# -.net
KiCad netlist of a schematic drawn in EasyEDA Pro
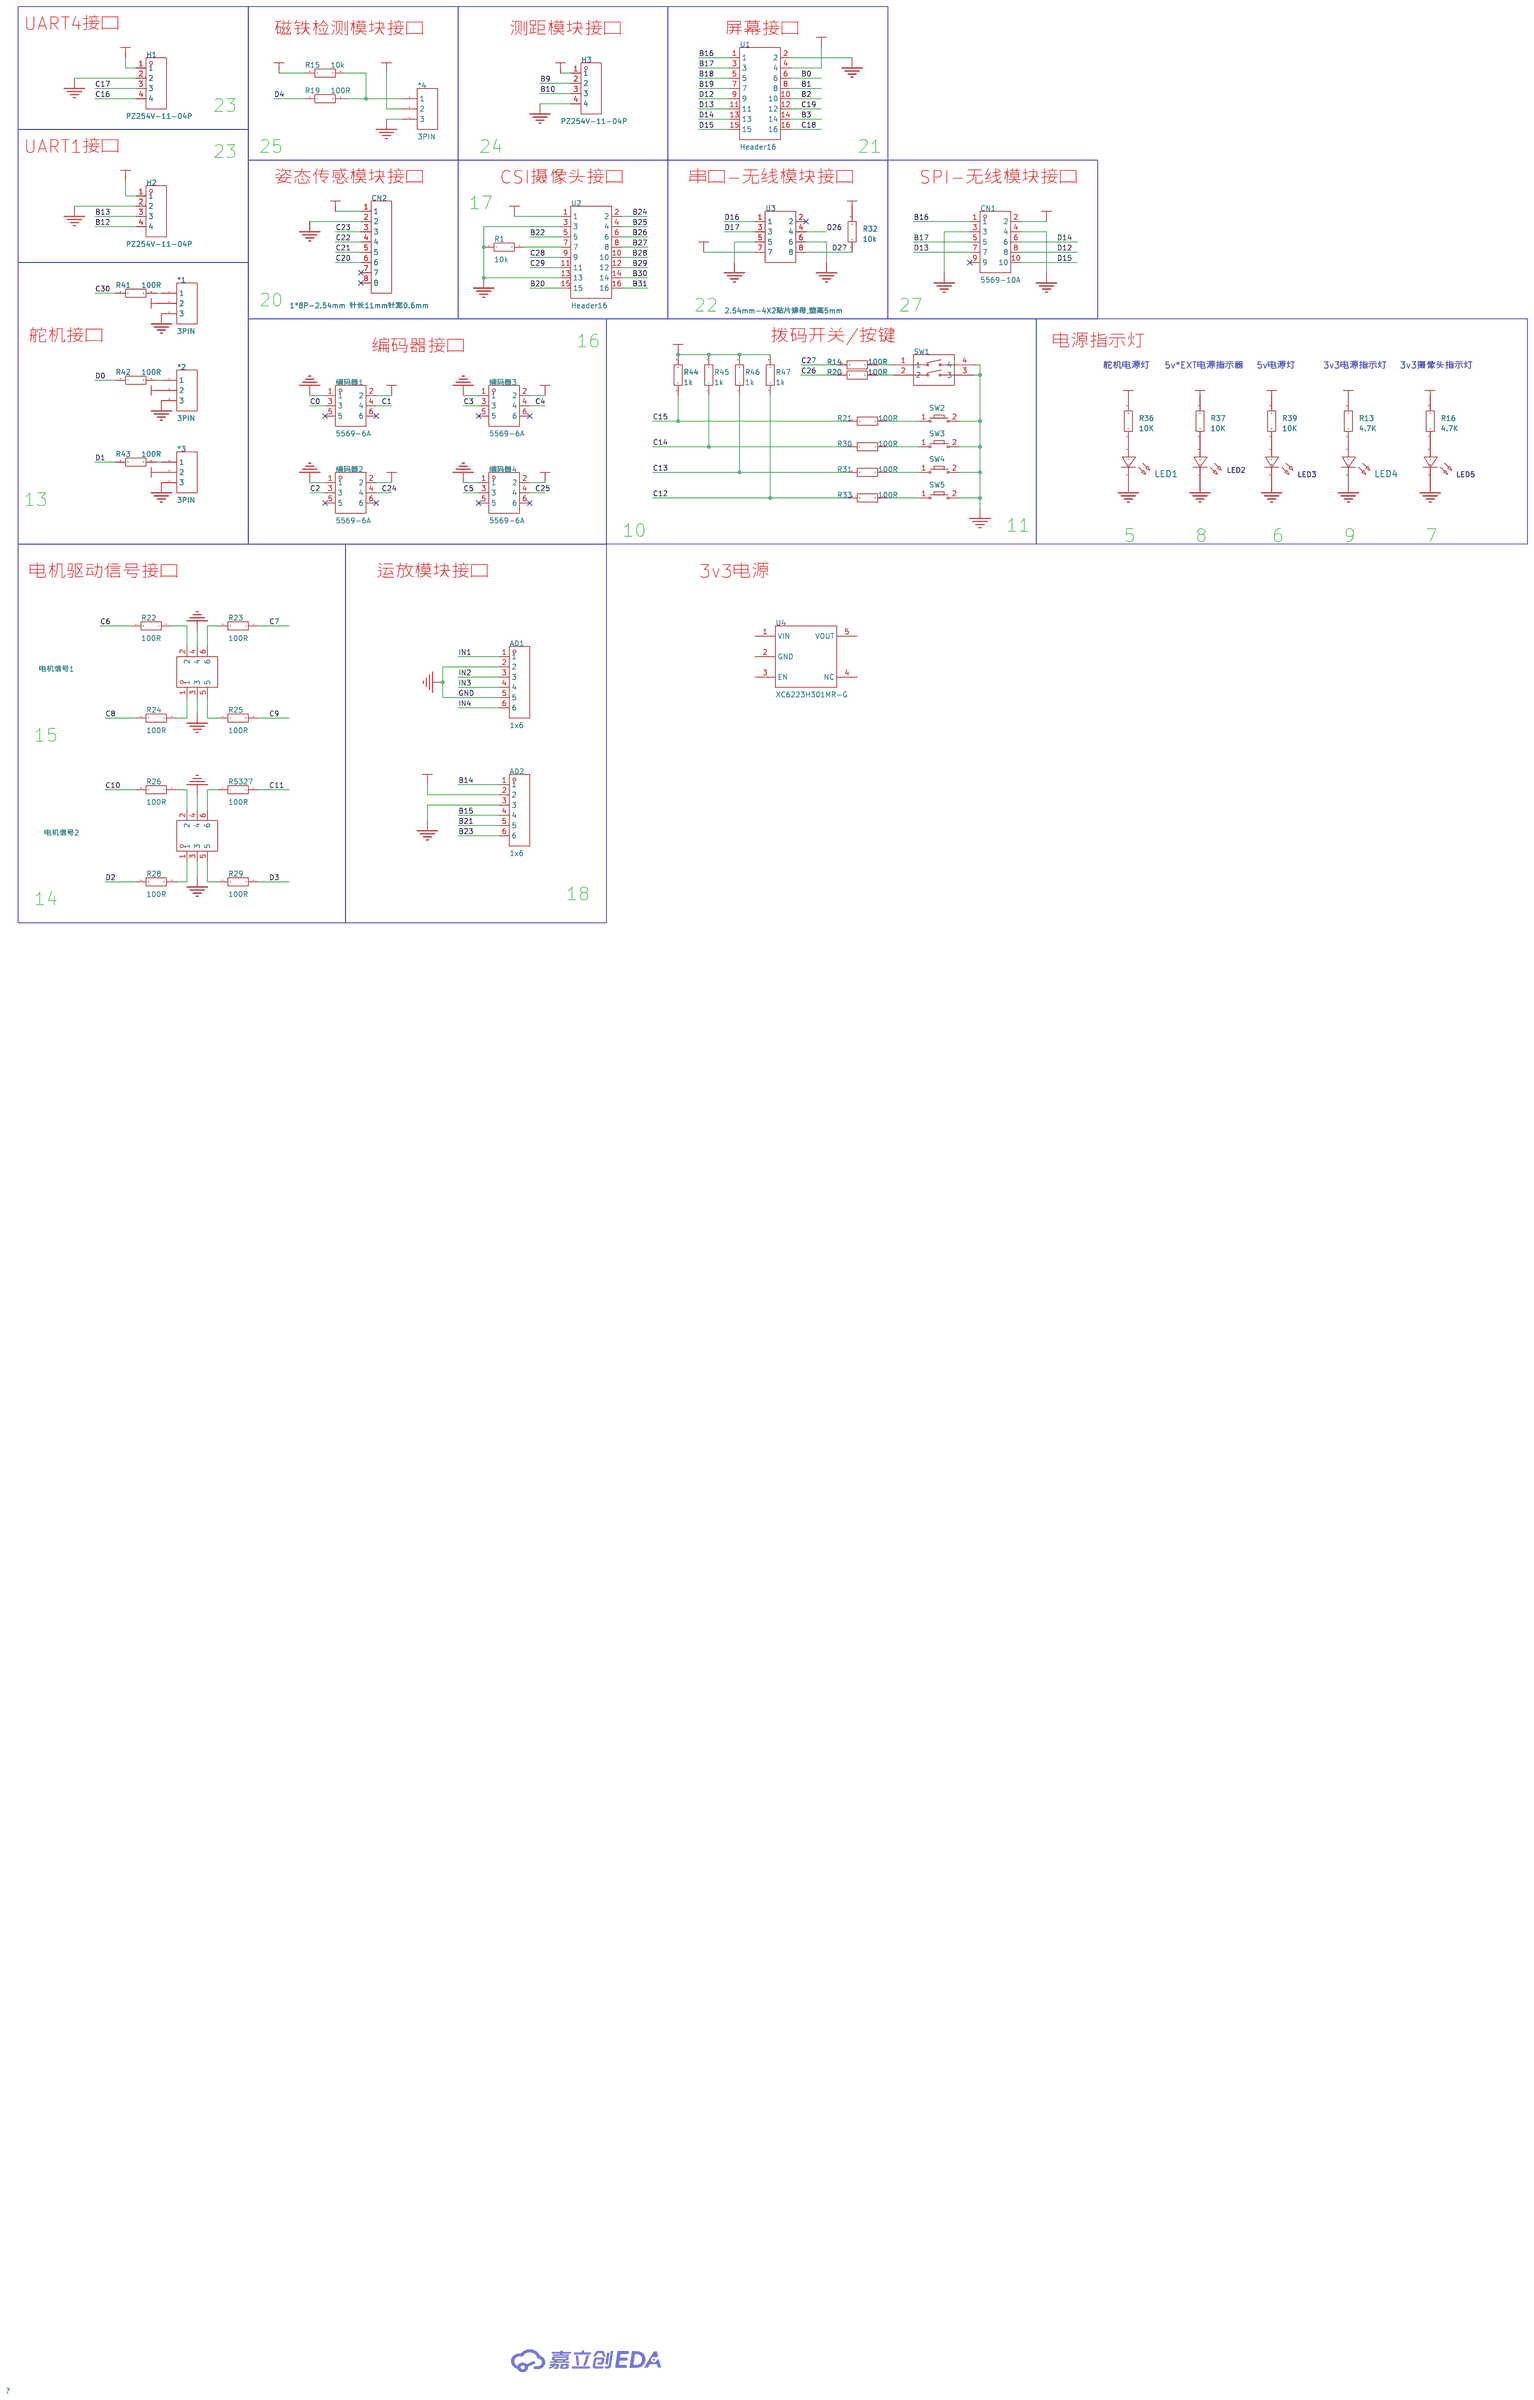
[diagram p0: schematic sheet]

(export (version "E")
  (design (tool "Eeschema 10.0.6"))
  (components
    (comp (ref "*1")
      (value "3PIN")
      (footprint "easyedapro:3PIN")
      (libsource (lib "easyedapro") (part "1*3PIN"))
    )
    (comp (ref "*2")
      (value "3PIN")
      (footprint "easyedapro:3PIN")
      (libsource (lib "easyedapro") (part "1*3PIN"))
    )
    (comp (ref "*3")
      (value "3PIN")
      (footprint "easyedapro:3PIN")
      (libsource (lib "easyedapro") (part "1*3PIN"))
    )
    (comp (ref "*4")
      (value "3PIN")
      (footprint "easyedapro:3PIN")
      (libsource (lib "easyedapro") (part "1*3PIN"))
    )
    (comp (ref "AD1")
      (value "1x6")
      (footprint "easyedapro:HDR-TH_6P-P2.54-V-F")
      (fields (field (name "Manufacturer Part") "Female header 1*6p") (field (name "Manufacturer") "BOOMELE"))
      (libsource (lib "easyedapro") (part "1x6"))
    )
    (comp (ref "AD2")
      (value "1x6")
      (footprint "easyedapro:HDR-TH_6P-P2.54-V-F")
      (fields (field (name "Manufacturer Part") "Female header 1*6p") (field (name "Manufacturer") "BOOMELE"))
      (libsource (lib "easyedapro") (part "1x6"))
    )
    (comp (ref "CN1")
      (value "5569-10A")
      (footprint "easyedapro:CONN-TH_10P-P4.20_5569-10A")
      (libsource (lib "easyedapro") (part "5569-10A"))
    )
    (comp (ref "CN2")
      (value "1*8P-2.54mm 针长11mm针宽0.6mm")
      (footprint "easyedapro:HDR-TH_8P-P2.54-V-F-S2.54")
      (libsource (lib "easyedapro") (part "1*8P-2.54MM 针长11MM针宽0.6MM"))
    )
    (comp (ref "H1")
      (value "PZ254V-11-04P")
      (footprint "easyedapro:HDR-TH_4P-P2.54-V-M")
      (fields (field (name "Manufacturer") "XFCN(兴飞)"))
      (libsource (lib "easyedapro") (part "PZ254V-11-04P_C2691448"))
    )
    (comp (ref "H2")
      (value "PZ254V-11-04P")
      (footprint "easyedapro:HDR-TH_4P-P2.54-V-M")
      (fields (field (name "Manufacturer") "XFCN(兴飞)"))
      (libsource (lib "easyedapro") (part "PZ254V-11-04P_C2691448"))
    )
    (comp (ref "H3")
      (value "PZ254V-11-04P")
      (footprint "easyedapro:HDR-TH_4P-P2.54-V-M")
      (fields (field (name "Manufacturer") "XFCN(兴飞)"))
      (libsource (lib "easyedapro") (part "PZ254V-11-04P_C2691448"))
    )
    (comp (ref "LED1")
      (value "~")
      (footprint "easyedapro:LED_0603")
      (libsource (lib "easyedapro") (part "LED_R"))
    )
    (comp (ref "LED2")
      (value "~")
      (footprint "easyedapro:LED_0603")
      (libsource (lib "easyedapro") (part "LED_G"))
    )
    (comp (ref "LED3")
      (value "~")
      (footprint "easyedapro:LED_0603")
      (libsource (lib "easyedapro") (part "LED_B"))
    )
    (comp (ref "LED4")
      (value "~")
      (footprint "easyedapro:LED_0603")
      (libsource (lib "easyedapro") (part "LED_R"))
    )
    (comp (ref "LED5")
      (value "~")
      (footprint "easyedapro:LED_0603")
      (libsource (lib "easyedapro") (part "LED_G"))
    )
    (comp (ref "R1")
      (value "10k")
      (footprint "easyedapro:R0603")
      (description "电阻类型:厚膜电阻;阻值:10kΩ;精度:±1%;功率:100mW;工作电压:75V;温度系数:±100ppm/°C;")
      (fields
        (field (name "Manufacturer Part") "0603WAF1002T5E")
        (field (name "Manufacturer") "UNI-ROYAL(厚声)")
      )
      (libsource (lib "easyedapro") (part "0603WAF1002T5E"))
    )
    (comp (ref "R13")
      (value "4.7K")
      (footprint "easyedapro:R0603")
      (libsource (lib "easyedapro") (part "电阻"))
    )
    (comp (ref "R14")
      (value "100Ω ±1% 62.5mW")
      (footprint "easyedapro:R0402")
      (fields
        (field (name "Manufacturer Part") "0402WGF1000TCE")
        (field (name "Manufacturer") "UNI-ROYAL(厚声)")
      )
      (libsource (lib "easyedapro") (part "0402WGF1000TCE"))
    )
    (comp (ref "R15")
      (value "10k")
      (footprint "easyedapro:R0603")
      (description "电阻类型:厚膜电阻;阻值:10kΩ;精度:±1%;功率:100mW;工作电压:75V;温度系数:±100ppm/°C;")
      (fields
        (field (name "Manufacturer Part") "0603WAF1002T5E")
        (field (name "Manufacturer") "UNI-ROYAL(厚声)")
      )
      (libsource (lib "easyedapro") (part "0603WAF1002T5E"))
    )
    (comp (ref "R16")
      (value "4.7K")
      (footprint "easyedapro:R0603")
      (libsource (lib "easyedapro") (part "电阻"))
    )
    (comp (ref "R19")
      (value "100Ω ±1% 62.5mW")
      (footprint "easyedapro:R0402")
      (fields
        (field (name "Manufacturer Part") "0402WGF1000TCE")
        (field (name "Manufacturer") "UNI-ROYAL(厚声)")
      )
      (libsource (lib "easyedapro") (part "0402WGF1000TCE"))
    )
    (comp (ref "R20")
      (value "100Ω ±1% 62.5mW")
      (footprint "easyedapro:R0402")
      (fields
        (field (name "Manufacturer Part") "0402WGF1000TCE")
        (field (name "Manufacturer") "UNI-ROYAL(厚声)")
      )
      (libsource (lib "easyedapro") (part "0402WGF1000TCE"))
    )
    (comp (ref "R21")
      (value "100Ω ±1% 62.5mW")
      (footprint "easyedapro:R0402")
      (fields
        (field (name "Manufacturer Part") "0402WGF1000TCE")
        (field (name "Manufacturer") "UNI-ROYAL(厚声)")
      )
      (libsource (lib "easyedapro") (part "0402WGF1000TCE"))
    )
    (comp (ref "R22")
      (value "100Ω ±1% 62.5mW")
      (footprint "easyedapro:R0402")
      (fields
        (field (name "Manufacturer Part") "0402WGF1000TCE")
        (field (name "Manufacturer") "UNI-ROYAL(厚声)")
      )
      (libsource (lib "easyedapro") (part "0402WGF1000TCE"))
    )
    (comp (ref "R23")
      (value "100Ω ±1% 62.5mW")
      (footprint "easyedapro:R0402")
      (fields
        (field (name "Manufacturer Part") "0402WGF1000TCE")
        (field (name "Manufacturer") "UNI-ROYAL(厚声)")
      )
      (libsource (lib "easyedapro") (part "0402WGF1000TCE"))
    )
    (comp (ref "R24")
      (value "100Ω ±1% 62.5mW")
      (footprint "easyedapro:R0402")
      (fields
        (field (name "Manufacturer Part") "0402WGF1000TCE")
        (field (name "Manufacturer") "UNI-ROYAL(厚声)")
      )
      (libsource (lib "easyedapro") (part "0402WGF1000TCE"))
    )
    (comp (ref "R25")
      (value "100Ω ±1% 62.5mW")
      (footprint "easyedapro:R0402")
      (fields
        (field (name "Manufacturer Part") "0402WGF1000TCE")
        (field (name "Manufacturer") "UNI-ROYAL(厚声)")
      )
      (libsource (lib "easyedapro") (part "0402WGF1000TCE"))
    )
    (comp (ref "R26")
      (value "100Ω ±1% 62.5mW")
      (footprint "easyedapro:R0402")
      (fields
        (field (name "Manufacturer Part") "0402WGF1000TCE")
        (field (name "Manufacturer") "UNI-ROYAL(厚声)")
      )
      (libsource (lib "easyedapro") (part "0402WGF1000TCE"))
    )
    (comp (ref "R28")
      (value "100Ω ±1% 62.5mW")
      (footprint "easyedapro:R0402")
      (fields
        (field (name "Manufacturer Part") "0402WGF1000TCE")
        (field (name "Manufacturer") "UNI-ROYAL(厚声)")
      )
      (libsource (lib "easyedapro") (part "0402WGF1000TCE"))
    )
    (comp (ref "R29")
      (value "100Ω ±1% 62.5mW")
      (footprint "easyedapro:R0402")
      (fields
        (field (name "Manufacturer Part") "0402WGF1000TCE")
        (field (name "Manufacturer") "UNI-ROYAL(厚声)")
      )
      (libsource (lib "easyedapro") (part "0402WGF1000TCE"))
    )
    (comp (ref "R30")
      (value "100Ω ±1% 62.5mW")
      (footprint "easyedapro:R0402")
      (fields
        (field (name "Manufacturer Part") "0402WGF1000TCE")
        (field (name "Manufacturer") "UNI-ROYAL(厚声)")
      )
      (libsource (lib "easyedapro") (part "0402WGF1000TCE"))
    )
    (comp (ref "R31")
      (value "100Ω ±1% 62.5mW")
      (footprint "easyedapro:R0402")
      (fields
        (field (name "Manufacturer Part") "0402WGF1000TCE")
        (field (name "Manufacturer") "UNI-ROYAL(厚声)")
      )
      (libsource (lib "easyedapro") (part "0402WGF1000TCE"))
    )
    (comp (ref "R32")
      (value "10k")
      (footprint "easyedapro:R0603")
      (description "电阻类型:厚膜电阻;阻值:10kΩ;精度:±1%;功率:100mW;工作电压:75V;温度系数:±100ppm/°C;")
      (fields
        (field (name "Manufacturer Part") "0603WAF1002T5E")
        (field (name "Manufacturer") "UNI-ROYAL(厚声)")
      )
      (libsource (lib "easyedapro") (part "0603WAF1002T5E"))
    )
    (comp (ref "R33")
      (value "100Ω ±1% 62.5mW")
      (footprint "easyedapro:R0402")
      (fields
        (field (name "Manufacturer Part") "0402WGF1000TCE")
        (field (name "Manufacturer") "UNI-ROYAL(厚声)")
      )
      (libsource (lib "easyedapro") (part "0402WGF1000TCE"))
    )
    (comp (ref "R36") (value "10K") (footprint "easyedapro:R0603") (libsource (lib "easyedapro") (part "电阻")))
    (comp (ref "R37") (value "10K") (footprint "easyedapro:R0603") (libsource (lib "easyedapro") (part "电阻")))
    (comp (ref "R39") (value "10K") (footprint "easyedapro:R0603") (libsource (lib "easyedapro") (part "电阻")))
    (comp (ref "R41")
      (value "100Ω ±1% 62.5mW")
      (footprint "easyedapro:R0402")
      (fields
        (field (name "Manufacturer Part") "0402WGF1000TCE")
        (field (name "Manufacturer") "UNI-ROYAL(厚声)")
      )
      (libsource (lib "easyedapro") (part "0402WGF1000TCE"))
    )
    (comp (ref "R42")
      (value "100Ω ±1% 62.5mW")
      (footprint "easyedapro:R0402")
      (fields
        (field (name "Manufacturer Part") "0402WGF1000TCE")
        (field (name "Manufacturer") "UNI-ROYAL(厚声)")
      )
      (libsource (lib "easyedapro") (part "0402WGF1000TCE"))
    )
    (comp (ref "R43")
      (value "100Ω ±1% 62.5mW")
      (footprint "easyedapro:R0402")
      (fields
        (field (name "Manufacturer Part") "0402WGF1000TCE")
        (field (name "Manufacturer") "UNI-ROYAL(厚声)")
      )
      (libsource (lib "easyedapro") (part "0402WGF1000TCE"))
    )
    (comp (ref "R44")
      (value "1k")
      (footprint "easyedapro:R0603")
      (description "电阻类型:厚膜电阻;阻值:10kΩ;精度:±1%;功率:100mW;工作电压:75V;温度系数:±100ppm/°C;")
      (fields
        (field (name "Manufacturer Part") "0603WAF1002T5E")
        (field (name "Manufacturer") "UNI-ROYAL(厚声)")
      )
      (libsource (lib "easyedapro") (part "0603WAF1002T5E"))
    )
    (comp (ref "R45")
      (value "1k")
      (footprint "easyedapro:R0603")
      (description "电阻类型:厚膜电阻;阻值:10kΩ;精度:±1%;功率:100mW;工作电压:75V;温度系数:±100ppm/°C;")
      (fields
        (field (name "Manufacturer Part") "0603WAF1002T5E")
        (field (name "Manufacturer") "UNI-ROYAL(厚声)")
      )
      (libsource (lib "easyedapro") (part "0603WAF1002T5E"))
    )
    (comp (ref "R46")
      (value "1k")
      (footprint "easyedapro:R0603")
      (description "电阻类型:厚膜电阻;阻值:10kΩ;精度:±1%;功率:100mW;工作电压:75V;温度系数:±100ppm/°C;")
      (fields
        (field (name "Manufacturer Part") "0603WAF1002T5E")
        (field (name "Manufacturer") "UNI-ROYAL(厚声)")
      )
      (libsource (lib "easyedapro") (part "0603WAF1002T5E"))
    )
    (comp (ref "R47")
      (value "1k")
      (footprint "easyedapro:R0603")
      (description "电阻类型:厚膜电阻;阻值:10kΩ;精度:±1%;功率:100mW;工作电压:75V;温度系数:±100ppm/°C;")
      (fields
        (field (name "Manufacturer Part") "0603WAF1002T5E")
        (field (name "Manufacturer") "UNI-ROYAL(厚声)")
      )
      (libsource (lib "easyedapro") (part "0603WAF1002T5E"))
    )
    (comp (ref "R5327")
      (value "100Ω ±1% 62.5mW")
      (footprint "easyedapro:R0402")
      (fields
        (field (name "Manufacturer Part") "0402WGF1000TCE")
        (field (name "Manufacturer") "UNI-ROYAL(厚声)")
      )
      (libsource (lib "easyedapro") (part "0402WGF1000TCE"))
    )
    (comp (ref "SW1")
      (value "CES-0202MC")
      (footprint "easyedapro:SW-TH_NIDEC_CES-0202MC")
      (description "特性：双镀金触点,接触稳定性极佳。符合RoHS标准。触感清脆。应用：热水设备。空调设备")
      (fields (field (name "Manufacturer") "NIDEC(尼得科)"))
      (libsource (lib "easyedapro") (part "CES-0202MC"))
    )
    (comp (ref "SW2")
      (value "~")
      (footprint "easyedapro:Key_SMD_3x4x2")
      (libsource (lib "easyedapro") (part "轻触按键x2"))
    )
    (comp (ref "SW3")
      (value "~")
      (footprint "easyedapro:Key_SMD_3x4x2")
      (libsource (lib "easyedapro") (part "轻触按键x2"))
    )
    (comp (ref "SW4")
      (value "~")
      (footprint "easyedapro:Key_SMD_3x4x2")
      (libsource (lib "easyedapro") (part "轻触按键x2"))
    )
    (comp (ref "SW5")
      (value "~")
      (footprint "easyedapro:Key_SMD_3x4x2")
      (libsource (lib "easyedapro") (part "轻触按键x2"))
    )
    (comp (ref "U1")
      (value "Header16")
      (footprint "easyedapro:CONN-TH_16P-P2.50_C9900044747")
      (libsource (lib "easyedapro") (part "HEADER16_C9900044747"))
    )
    (comp (ref "U2")
      (value "Header16")
      (footprint "easyedapro:CONN-TH_16P-P2.50_C9900044747")
      (libsource (lib "easyedapro") (part "HEADER16_C9900044747"))
    )
    (comp (ref "U3")
      (value "2.54mm-4X2贴片排母,塑高5mm")
      (footprint "easyedapro:HDR-SMD_8P-P2.54-V-F-R2-C4-S7.1")
      (libsource (lib "easyedapro") (part "2.54MM-4X2贴片排母,塑高5MM"))
    )
    (comp (ref "U4") (value "XC6223H301MR-G") (libsource (lib "easyedapro") (part "RT9013")))
    (comp (ref "电机信号1")
      (value "5569-6A")
      (footprint "easyedapro:CONN-TH_6P-P4.20_5569-6A-1")
      (libsource (lib "easyedapro") (part "5569-6A"))
    )
    (comp (ref "电机信号2")
      (value "5569-6A")
      (footprint "easyedapro:CONN-TH_6P-P4.20_5569-6A-1")
      (libsource (lib "easyedapro") (part "5569-6A"))
    )
    (comp (ref "编码器1")
      (value "5569-6A")
      (footprint "easyedapro:CONN-TH_6P-P4.20_5569-6A-1")
      (libsource (lib "easyedapro") (part "5569-6A"))
    )
    (comp (ref "编码器2")
      (value "5569-6A")
      (footprint "easyedapro:CONN-TH_6P-P4.20_5569-6A-1")
      (libsource (lib "easyedapro") (part "5569-6A"))
    )
    (comp (ref "编码器3")
      (value "5569-6A")
      (footprint "easyedapro:CONN-TH_6P-P4.20_5569-6A-1")
      (libsource (lib "easyedapro") (part "5569-6A"))
    )
    (comp (ref "编码器4")
      (value "5569-6A")
      (footprint "easyedapro:CONN-TH_6P-P4.20_5569-6A-1")
      (libsource (lib "easyedapro") (part "5569-6A"))
    )
  )
  (nets
    (net (code "1") (name "/B0") (class "Default")
      (node (ref "U1") (pin "6") (pinfunction "6_6") (pintype "unspecified"))
    )
    (net (code "2") (name "/B1") (class "Default")
      (node (ref "U1") (pin "8") (pinfunction "8_8") (pintype "unspecified"))
    )
    (net (code "3") (name "/B2") (class "Default")
      (node (ref "U1") (pin "10") (pinfunction "10_10") (pintype "unspecified"))
    )
    (net (code "4") (name "/B3") (class "Default")
      (node (ref "U1") (pin "14") (pinfunction "14_14") (pintype "unspecified"))
    )
    (net (code "5") (name "/B9") (class "Default")
      (node (ref "H3") (pin "2") (pinfunction "2_2") (pintype "unspecified"))
    )
    (net (code "6") (name "/B10") (class "Default")
      (node (ref "H3") (pin "3") (pinfunction "3_3") (pintype "unspecified"))
    )
    (net (code "7") (name "/B12") (class "Default")
      (node (ref "H2") (pin "4") (pinfunction "4_4") (pintype "unspecified"))
    )
    (net (code "8") (name "/B13") (class "Default")
      (node (ref "H2") (pin "3") (pinfunction "3_3") (pintype "unspecified"))
    )
    (net (code "9") (name "/B14") (class "Default")
      (node (ref "AD2") (pin "1") (pinfunction "1_1") (pintype "unspecified"))
    )
    (net (code "10") (name "/B15") (class "Default")
      (node (ref "AD2") (pin "4") (pinfunction "4_4") (pintype "unspecified"))
    )
    (net (code "11") (name "/B16") (class "Default")
      (node (ref "CN1") (pin "1") (pinfunction "1_1") (pintype "unspecified"))
      (node (ref "U1") (pin "1") (pinfunction "1_1") (pintype "unspecified"))
    )
    (net (code "12") (name "/B17") (class "Default")
      (node (ref "CN1") (pin "5") (pinfunction "5_5") (pintype "unspecified"))
      (node (ref "U1") (pin "3") (pinfunction "3_3") (pintype "unspecified"))
    )
    (net (code "13") (name "/B18") (class "Default")
      (node (ref "U1") (pin "5") (pinfunction "5_5") (pintype "unspecified"))
    )
    (net (code "14") (name "/B19") (class "Default")
      (node (ref "U1") (pin "7") (pinfunction "7_7") (pintype "unspecified"))
    )
    (net (code "15") (name "/B20") (class "Default")
      (node (ref "U2") (pin "15") (pinfunction "15_15") (pintype "unspecified"))
    )
    (net (code "16") (name "/B21") (class "Default")
      (node (ref "AD2") (pin "5") (pinfunction "5_5") (pintype "unspecified"))
    )
    (net (code "17") (name "/B22") (class "Default")
      (node (ref "U2") (pin "5") (pinfunction "5_5") (pintype "unspecified"))
    )
    (net (code "18") (name "/B23") (class "Default")
      (node (ref "AD2") (pin "6") (pinfunction "6_6") (pintype "unspecified"))
    )
    (net (code "19") (name "/B24") (class "Default")
      (node (ref "U2") (pin "2") (pinfunction "2_2") (pintype "unspecified"))
    )
    (net (code "20") (name "/B25") (class "Default")
      (node (ref "U2") (pin "4") (pinfunction "4_4") (pintype "unspecified"))
    )
    (net (code "21") (name "/B26") (class "Default")
      (node (ref "U2") (pin "6") (pinfunction "6_6") (pintype "unspecified"))
    )
    (net (code "22") (name "/B27") (class "Default")
      (node (ref "U2") (pin "8") (pinfunction "8_8") (pintype "unspecified"))
    )
    (net (code "23") (name "/B28") (class "Default")
      (node (ref "U2") (pin "10") (pinfunction "10_10") (pintype "unspecified"))
    )
    (net (code "24") (name "/B29") (class "Default")
      (node (ref "U2") (pin "12") (pinfunction "12_12") (pintype "unspecified"))
    )
    (net (code "25") (name "/B30") (class "Default")
      (node (ref "U2") (pin "14") (pinfunction "14_14") (pintype "unspecified"))
    )
    (net (code "26") (name "/B31") (class "Default")
      (node (ref "U2") (pin "16") (pinfunction "16_16") (pintype "unspecified"))
    )
    (net (code "27") (name "/C0") (class "Default")
      (node (ref "编码器1") (pin "3") (pinfunction "3_3") (pintype "unspecified"))
    )
    (net (code "28") (name "/C1") (class "Default")
      (node (ref "编码器1") (pin "4") (pinfunction "4_4") (pintype "unspecified"))
    )
    (net (code "29") (name "/C2") (class "Default")
      (node (ref "编码器2") (pin "3") (pinfunction "3_3") (pintype "unspecified"))
    )
    (net (code "30") (name "/C3") (class "Default")
      (node (ref "编码器3") (pin "3") (pinfunction "3_3") (pintype "unspecified"))
    )
    (net (code "31") (name "/C4") (class "Default")
      (node (ref "编码器3") (pin "4") (pinfunction "4_4") (pintype "unspecified"))
    )
    (net (code "32") (name "/C5") (class "Default")
      (node (ref "编码器4") (pin "3") (pinfunction "3_3") (pintype "unspecified"))
    )
    (net (code "33") (name "/C6") (class "Default")
      (node (ref "R22") (pin "2") (pinfunction "2_2") (pintype "input"))
    )
    (net (code "34") (name "/C7") (class "Default")
      (node (ref "R23") (pin "1") (pinfunction "1_1") (pintype "input"))
    )
    (net (code "35") (name "/C8") (class "Default")
      (node (ref "R24") (pin "2") (pinfunction "2_2") (pintype "input"))
    )
    (net (code "36") (name "/C9") (class "Default")
      (node (ref "R25") (pin "2") (pinfunction "2_2") (pintype "input"))
    )
    (net (code "37") (name "/C10") (class "Default")
      (node (ref "R26") (pin "2") (pinfunction "2_2") (pintype "input"))
    )
    (net (code "38") (name "/C11") (class "Default")
      (node (ref "R5327") (pin "1") (pinfunction "1_1") (pintype "input"))
    )
    (net (code "39") (name "/C12") (class "Default")
      (node (ref "R33") (pin "2") (pinfunction "2_2") (pintype "input"))
      (node (ref "R47") (pin "1") (pinfunction "1_1") (pintype "input"))
    )
    (net (code "40") (name "/C13") (class "Default")
      (node (ref "R31") (pin "2") (pinfunction "2_2") (pintype "input"))
      (node (ref "R46") (pin "1") (pinfunction "1_1") (pintype "input"))
    )
    (net (code "41") (name "/C14") (class "Default")
      (node (ref "R30") (pin "2") (pinfunction "2_2") (pintype "input"))
      (node (ref "R45") (pin "1") (pinfunction "1_1") (pintype "input"))
    )
    (net (code "42") (name "/C15") (class "Default")
      (node (ref "R21") (pin "2") (pinfunction "2_2") (pintype "input"))
      (node (ref "R44") (pin "1") (pinfunction "1_1") (pintype "input"))
    )
    (net (code "43") (name "/C16") (class "Default")
      (node (ref "H1") (pin "4") (pinfunction "4_4") (pintype "unspecified"))
    )
    (net (code "44") (name "/C17") (class "Default")
      (node (ref "H1") (pin "3") (pinfunction "3_3") (pintype "unspecified"))
    )
    (net (code "45") (name "/C18") (class "Default")
      (node (ref "U1") (pin "16") (pinfunction "16_16") (pintype "unspecified"))
    )
    (net (code "46") (name "/C19") (class "Default")
      (node (ref "U1") (pin "12") (pinfunction "12_12") (pintype "unspecified"))
    )
    (net (code "47") (name "/C20") (class "Default")
      (node (ref "CN2") (pin "6") (pinfunction "6_6") (pintype "unspecified"))
    )
    (net (code "48") (name "/C21") (class "Default")
      (node (ref "CN2") (pin "5") (pinfunction "5_5") (pintype "unspecified"))
    )
    (net (code "49") (name "/C22") (class "Default")
      (node (ref "CN2") (pin "4") (pinfunction "4_4") (pintype "unspecified"))
    )
    (net (code "50") (name "/C23") (class "Default")
      (node (ref "CN2") (pin "3") (pinfunction "3_3") (pintype "unspecified"))
    )
    (net (code "51") (name "/C24") (class "Default")
      (node (ref "编码器2") (pin "4") (pinfunction "4_4") (pintype "unspecified"))
    )
    (net (code "52") (name "/C25") (class "Default")
      (node (ref "编码器4") (pin "4") (pinfunction "4_4") (pintype "unspecified"))
    )
    (net (code "53") (name "/C26") (class "Default")
      (node (ref "R20") (pin "2") (pinfunction "2_2") (pintype "input"))
    )
    (net (code "54") (name "/C27") (class "Default")
      (node (ref "R14") (pin "2") (pinfunction "2_2") (pintype "input"))
    )
    (net (code "55") (name "/C28") (class "Default")
      (node (ref "U2") (pin "9") (pinfunction "9_9") (pintype "unspecified"))
    )
    (net (code "56") (name "/C29") (class "Default")
      (node (ref "U2") (pin "11") (pinfunction "11_11") (pintype "unspecified"))
    )
    (net (code "57") (name "/C30") (class "Default")
      (node (ref "R41") (pin "1") (pinfunction "1_1") (pintype "input"))
    )
    (net (code "58") (name "/D0") (class "Default")
      (node (ref "R42") (pin "1") (pinfunction "1_1") (pintype "input"))
    )
    (net (code "59") (name "/D1") (class "Default")
      (node (ref "R43") (pin "1") (pinfunction "1_1") (pintype "input"))
    )
    (net (code "60") (name "/D2") (class "Default")
      (node (ref "R28") (pin "2") (pinfunction "2_2") (pintype "input"))
    )
    (net (code "61") (name "/D3") (class "Default")
      (node (ref "R29") (pin "2") (pinfunction "2_2") (pintype "input"))
    )
    (net (code "62") (name "/D4") (class "Default")
      (node (ref "R19") (pin "1") (pinfunction "1_1") (pintype "input"))
    )
    (net (code "63") (name "/D12") (class "Default")
      (node (ref "CN1") (pin "8") (pinfunction "8_8") (pintype "unspecified"))
      (node (ref "U1") (pin "9") (pinfunction "9_9") (pintype "unspecified"))
    )
    (net (code "64") (name "/D13") (class "Default")
      (node (ref "CN1") (pin "7") (pinfunction "7_7") (pintype "unspecified"))
      (node (ref "U1") (pin "11") (pinfunction "11_11") (pintype "unspecified"))
    )
    (net (code "65") (name "/D14") (class "Default")
      (node (ref "CN1") (pin "6") (pinfunction "6_6") (pintype "unspecified"))
      (node (ref "U1") (pin "13") (pinfunction "13_13") (pintype "unspecified"))
    )
    (net (code "66") (name "/D15") (class "Default")
      (node (ref "CN1") (pin "10") (pinfunction "10_10") (pintype "unspecified"))
      (node (ref "U1") (pin "15") (pinfunction "15_15") (pintype "unspecified"))
    )
    (net (code "67") (name "/D16") (class "Default")
      (node (ref "U3") (pin "1") (pinfunction "1_1") (pintype "unspecified"))
    )
    (net (code "68") (name "/D17") (class "Default")
      (node (ref "U3") (pin "3") (pinfunction "3_3") (pintype "unspecified"))
    )
    (net (code "69") (name "/D26") (class "Default")
      (node (ref "U3") (pin "4") (pinfunction "4_4") (pintype "unspecified"))
    )
    (net (code "70") (name "/D27") (class "Default")
      (node (ref "R32") (pin "1") (pinfunction "1_1") (pintype "input"))
      (node (ref "U3") (pin "8") (pinfunction "8_8") (pintype "unspecified"))
    )
    (net (code "71") (name "/IN1") (class "Default")
      (node (ref "AD1") (pin "1") (pinfunction "1_1") (pintype "unspecified"))
    )
    (net (code "72") (name "/IN2") (class "Default")
      (node (ref "AD1") (pin "3") (pinfunction "3_3") (pintype "unspecified"))
    )
    (net (code "73") (name "/IN3") (class "Default")
      (node (ref "AD1") (pin "4") (pinfunction "4_4") (pintype "unspecified"))
    )
    (net (code "74") (name "/IN4") (class "Default")
      (node (ref "AD1") (pin "6") (pinfunction "6_6") (pintype "unspecified"))
    )
    (net (code "75") (name "3V3") (class "Default")
      (node (ref "*4") (pin "2") (pinfunction "2_2") (pintype "unspecified"))
      (node (ref "AD2") (pin "2") (pinfunction "2_2") (pintype "unspecified"))
      (node (ref "CN2") (pin "1") (pinfunction "1_1") (pintype "unspecified"))
      (node (ref "H3") (pin "1") (pinfunction "1_1") (pintype "unspecified"))
      (node (ref "R13") (pin "2") (pinfunction "2_2") (pintype "input"))
      (node (ref "R15") (pin "1") (pinfunction "1_1") (pintype "input"))
      (node (ref "R32") (pin "2") (pinfunction "2_2") (pintype "input"))
      (node (ref "R44") (pin "2") (pinfunction "2_2") (pintype "input"))
      (node (ref "R45") (pin "2") (pinfunction "2_2") (pintype "input"))
      (node (ref "R46") (pin "2") (pinfunction "2_2") (pintype "input"))
      (node (ref "R47") (pin "2") (pinfunction "2_2") (pintype "input"))
      (node (ref "U1") (pin "4") (pinfunction "4_4") (pintype "unspecified"))
      (node (ref "编码器1") (pin "2") (pinfunction "2_2") (pintype "unspecified"))
      (node (ref "编码器2") (pin "2") (pinfunction "2_2") (pintype "unspecified"))
      (node (ref "编码器3") (pin "2") (pinfunction "2_2") (pintype "unspecified"))
      (node (ref "编码器4") (pin "2") (pinfunction "2_2") (pintype "unspecified"))
    )
    (net (code "76") (name "CSI-3V3") (class "Default")
      (node (ref "R16") (pin "2") (pinfunction "2_2") (pintype "input"))
      (node (ref "U2") (pin "1") (pinfunction "1_1") (pintype "unspecified"))
    )
    (net (code "77") (name "GND") (class "Default")
      (node (ref "*1") (pin "3") (pinfunction "3_3") (pintype "unspecified"))
      (node (ref "*2") (pin "3") (pinfunction "3_3") (pintype "unspecified"))
      (node (ref "*3") (pin "3") (pinfunction "3_3") (pintype "unspecified"))
      (node (ref "*4") (pin "3") (pinfunction "3_3") (pintype "unspecified"))
      (node (ref "AD1") (pin "2") (pinfunction "2_2") (pintype "unspecified"))
      (node (ref "AD1") (pin "5") (pinfunction "5_5") (pintype "unspecified"))
      (node (ref "AD2") (pin "3") (pinfunction "3_3") (pintype "unspecified"))
      (node (ref "CN1") (pin "3") (pinfunction "3_3") (pintype "unspecified"))
      (node (ref "CN1") (pin "4") (pinfunction "4_4") (pintype "unspecified"))
      (node (ref "CN2") (pin "2") (pinfunction "2_2") (pintype "unspecified"))
      (node (ref "H1") (pin "2") (pinfunction "2_2") (pintype "unspecified"))
      (node (ref "H2") (pin "2") (pinfunction "2_2") (pintype "unspecified"))
      (node (ref "H3") (pin "4") (pinfunction "4_4") (pintype "unspecified"))
      (node (ref "LED1") (pin "1") (pinfunction "C_1") (pintype "input"))
      (node (ref "LED2") (pin "1") (pinfunction "C_1") (pintype "input"))
      (node (ref "LED3") (pin "1") (pinfunction "C_1") (pintype "input"))
      (node (ref "LED4") (pin "1") (pinfunction "C_1") (pintype "input"))
      (node (ref "LED5") (pin "1") (pinfunction "C_1") (pintype "input"))
      (node (ref "R1") (pin "1") (pinfunction "1_1") (pintype "input"))
      (node (ref "SW1") (pin "3") (pinfunction "3_3") (pintype "unspecified"))
      (node (ref "SW1") (pin "4") (pinfunction "4_4") (pintype "unspecified"))
      (node (ref "SW2") (pin "2") (pinfunction "2_2") (pintype "input"))
      (node (ref "SW3") (pin "2") (pinfunction "2_2") (pintype "input"))
      (node (ref "SW4") (pin "2") (pinfunction "2_2") (pintype "input"))
      (node (ref "SW5") (pin "2") (pinfunction "2_2") (pintype "input"))
      (node (ref "U1") (pin "2") (pinfunction "2_2") (pintype "unspecified"))
      (node (ref "U2") (pin "13") (pinfunction "13_13") (pintype "unspecified"))
      (node (ref "U2") (pin "3") (pinfunction "3_3") (pintype "unspecified"))
      (node (ref "U3") (pin "5") (pinfunction "5_5") (pintype "unspecified"))
      (node (ref "U3") (pin "6") (pinfunction "6_6") (pintype "unspecified"))
      (node (ref "电机信号1") (pin "3") (pinfunction "3_3") (pintype "unspecified"))
      (node (ref "电机信号1") (pin "4") (pinfunction "4_4") (pintype "unspecified"))
      (node (ref "电机信号2") (pin "3") (pinfunction "3_3") (pintype "unspecified"))
      (node (ref "电机信号2") (pin "4") (pinfunction "4_4") (pintype "unspecified"))
      (node (ref "编码器1") (pin "1") (pinfunction "1_1") (pintype "unspecified"))
      (node (ref "编码器2") (pin "1") (pinfunction "1_1") (pintype "unspecified"))
      (node (ref "编码器3") (pin "1") (pinfunction "1_1") (pintype "unspecified"))
      (node (ref "编码器4") (pin "1") (pinfunction "1_1") (pintype "unspecified"))
    )
    (net (code "78") (name "Net-(*1-Pad1)") (class "Default")
      (node (ref "*1") (pin "1") (pinfunction "1_1") (pintype "unspecified"))
      (node (ref "R41") (pin "2") (pinfunction "2_2") (pintype "input"))
    )
    (net (code "79") (name "Net-(*2-Pad1)") (class "Default")
      (node (ref "*2") (pin "1") (pinfunction "1_1") (pintype "unspecified"))
      (node (ref "R42") (pin "2") (pinfunction "2_2") (pintype "input"))
    )
    (net (code "80") (name "Net-(*3-Pad1)") (class "Default")
      (node (ref "*3") (pin "1") (pinfunction "1_1") (pintype "unspecified"))
      (node (ref "R43") (pin "2") (pinfunction "2_2") (pintype "input"))
    )
    (net (code "81") (name "Net-(*4-Pad1)") (class "Default")
      (node (ref "*4") (pin "1") (pinfunction "1_1") (pintype "unspecified"))
      (node (ref "R15") (pin "2") (pinfunction "2_2") (pintype "input"))
      (node (ref "R19") (pin "2") (pinfunction "2_2") (pintype "input"))
    )
    (net (code "82") (name "Net-(LED1-A)") (class "Default")
      (node (ref "LED1") (pin "2") (pinfunction "A_2") (pintype "input"))
      (node (ref "R36") (pin "1") (pinfunction "1_1") (pintype "input"))
    )
    (net (code "83") (name "Net-(LED2-A)") (class "Default")
      (node (ref "LED2") (pin "2") (pinfunction "A_2") (pintype "input"))
      (node (ref "R37") (pin "1") (pinfunction "1_1") (pintype "input"))
    )
    (net (code "84") (name "Net-(LED3-A)") (class "Default")
      (node (ref "LED3") (pin "2") (pinfunction "A_2") (pintype "input"))
      (node (ref "R39") (pin "1") (pinfunction "1_1") (pintype "input"))
    )
    (net (code "85") (name "Net-(LED4-A)") (class "Default")
      (node (ref "LED4") (pin "2") (pinfunction "A_2") (pintype "input"))
      (node (ref "R13") (pin "1") (pinfunction "1_1") (pintype "input"))
    )
    (net (code "86") (name "Net-(LED5-A)") (class "Default")
      (node (ref "LED5") (pin "2") (pinfunction "A_2") (pintype "input"))
      (node (ref "R16") (pin "1") (pinfunction "1_1") (pintype "input"))
    )
    (net (code "87") (name "Net-(R1-Pad2)") (class "Default")
      (node (ref "R1") (pin "2") (pinfunction "2_2") (pintype "input"))
      (node (ref "U2") (pin "7") (pinfunction "7_7") (pintype "unspecified"))
    )
    (net (code "88") (name "Net-(R14-Pad1)") (class "Default")
      (node (ref "R14") (pin "1") (pinfunction "1_1") (pintype "input"))
      (node (ref "SW1") (pin "1") (pinfunction "1_1") (pintype "unspecified"))
    )
    (net (code "89") (name "Net-(R20-Pad1)") (class "Default")
      (node (ref "R20") (pin "1") (pinfunction "1_1") (pintype "input"))
      (node (ref "SW1") (pin "2") (pinfunction "2_2") (pintype "unspecified"))
    )
    (net (code "90") (name "Net-(R21-Pad1)") (class "Default")
      (node (ref "R21") (pin "1") (pinfunction "1_1") (pintype "input"))
      (node (ref "SW2") (pin "1") (pinfunction "1_1") (pintype "input"))
    )
    (net (code "91") (name "Net-(R22-Pad1)") (class "Default")
      (node (ref "R22") (pin "1") (pinfunction "1_1") (pintype "input"))
      (node (ref "电机信号1") (pin "2") (pinfunction "2_2") (pintype "unspecified"))
    )
    (net (code "92") (name "Net-(R23-Pad2)") (class "Default")
      (node (ref "R23") (pin "2") (pinfunction "2_2") (pintype "input"))
      (node (ref "电机信号1") (pin "6") (pinfunction "6_6") (pintype "unspecified"))
    )
    (net (code "93") (name "Net-(R24-Pad1)") (class "Default")
      (node (ref "R24") (pin "1") (pinfunction "1_1") (pintype "input"))
      (node (ref "电机信号1") (pin "1") (pinfunction "1_1") (pintype "unspecified"))
    )
    (net (code "94") (name "Net-(R25-Pad1)") (class "Default")
      (node (ref "R25") (pin "1") (pinfunction "1_1") (pintype "input"))
      (node (ref "电机信号1") (pin "5") (pinfunction "5_5") (pintype "unspecified"))
    )
    (net (code "95") (name "Net-(R26-Pad1)") (class "Default")
      (node (ref "R26") (pin "1") (pinfunction "1_1") (pintype "input"))
      (node (ref "电机信号2") (pin "2") (pinfunction "2_2") (pintype "unspecified"))
    )
    (net (code "96") (name "Net-(R28-Pad1)") (class "Default")
      (node (ref "R28") (pin "1") (pinfunction "1_1") (pintype "input"))
      (node (ref "电机信号2") (pin "1") (pinfunction "1_1") (pintype "unspecified"))
    )
    (net (code "97") (name "Net-(R29-Pad1)") (class "Default")
      (node (ref "R29") (pin "1") (pinfunction "1_1") (pintype "input"))
      (node (ref "电机信号2") (pin "5") (pinfunction "5_5") (pintype "unspecified"))
    )
    (net (code "98") (name "Net-(R30-Pad1)") (class "Default")
      (node (ref "R30") (pin "1") (pinfunction "1_1") (pintype "input"))
      (node (ref "SW3") (pin "1") (pinfunction "1_1") (pintype "input"))
    )
    (net (code "99") (name "Net-(R31-Pad1)") (class "Default")
      (node (ref "R31") (pin "1") (pinfunction "1_1") (pintype "input"))
      (node (ref "SW4") (pin "1") (pinfunction "1_1") (pintype "input"))
    )
    (net (code "100") (name "Net-(R33-Pad1)") (class "Default")
      (node (ref "R33") (pin "1") (pinfunction "1_1") (pintype "input"))
      (node (ref "SW5") (pin "1") (pinfunction "1_1") (pintype "input"))
    )
    (net (code "101") (name "Net-(R5327-Pad2)") (class "Default")
      (node (ref "R5327") (pin "2") (pinfunction "2_2") (pintype "input"))
      (node (ref "电机信号2") (pin "6") (pinfunction "6_6") (pintype "unspecified"))
    )
    (net (code "102") (name "VCC-5V") (class "Default")
      (node (ref "R39") (pin "2") (pinfunction "2_2") (pintype "input"))
    )
    (net (code "103") (name "VCC-5V-EXT") (class "Default")
      (node (ref "CN1") (pin "2") (pinfunction "2_2") (pintype "unspecified"))
      (node (ref "H1") (pin "1") (pinfunction "1_1") (pintype "unspecified"))
      (node (ref "H2") (pin "1") (pinfunction "1_1") (pintype "unspecified"))
      (node (ref "R37") (pin "2") (pinfunction "2_2") (pintype "input"))
      (node (ref "U3") (pin "7") (pinfunction "7_7") (pintype "unspecified"))
    )
    (net (code "104") (name "VCC_SERVO") (class "Default")
      (node (ref "*1") (pin "2") (pinfunction "2_2") (pintype "unspecified"))
      (node (ref "*2") (pin "2") (pinfunction "2_2") (pintype "unspecified"))
      (node (ref "*3") (pin "2") (pinfunction "2_2") (pintype "unspecified"))
      (node (ref "R36") (pin "2") (pinfunction "2_2") (pintype "input"))
    )
    (net (code "105") (name "unconnected-(CN1-Pad9)") (class "Default")
      (node (ref "CN1") (pin "9") (pinfunction "9_9") (pintype "unspecified+no_connect"))
    )
    (net (code "106") (name "unconnected-(CN2-Pad7)") (class "Default")
      (node (ref "CN2") (pin "7") (pinfunction "7_7") (pintype "unspecified+no_connect"))
    )
    (net (code "107") (name "unconnected-(CN2-Pad8)") (class "Default")
      (node (ref "CN2") (pin "8") (pinfunction "8_8") (pintype "unspecified+no_connect"))
    )
    (net (code "108") (name "unconnected-(U3-Pad2)") (class "Default")
      (node (ref "U3") (pin "2") (pinfunction "2_2") (pintype "unspecified+no_connect"))
    )
    (net (code "109") (name "unconnected-(U4-EN-Pad3)") (class "Default")
      (node (ref "U4") (pin "3") (pinfunction "EN_3") (pintype "input"))
    )
    (net (code "110") (name "unconnected-(U4-GND-Pad2)") (class "Default")
      (node (ref "U4") (pin "2") (pinfunction "GND_2") (pintype "input"))
    )
    (net (code "111") (name "unconnected-(U4-NC-Pad4)") (class "Default")
      (node (ref "U4") (pin "4") (pinfunction "NC_4") (pintype "input"))
    )
    (net (code "112") (name "unconnected-(U4-VIN-Pad1)") (class "Default")
      (node (ref "U4") (pin "1") (pinfunction "VIN_1") (pintype "input"))
    )
    (net (code "113") (name "unconnected-(U4-VOUT-Pad5)") (class "Default")
      (node (ref "U4") (pin "5") (pinfunction "VOUT_5") (pintype "input"))
    )
    (net (code "114") (name "unconnected-(编码器1-Pad5)") (class "Default")
      (node (ref "编码器1") (pin "5") (pinfunction "5_5") (pintype "unspecified+no_connect"))
    )
    (net (code "115") (name "unconnected-(编码器1-Pad6)") (class "Default")
      (node (ref "编码器1") (pin "6") (pinfunction "6_6") (pintype "unspecified+no_connect"))
    )
    (net (code "116") (name "unconnected-(编码器2-Pad5)") (class "Default")
      (node (ref "编码器2") (pin "5") (pinfunction "5_5") (pintype "unspecified+no_connect"))
    )
    (net (code "117") (name "unconnected-(编码器2-Pad6)") (class "Default")
      (node (ref "编码器2") (pin "6") (pinfunction "6_6") (pintype "unspecified+no_connect"))
    )
    (net (code "118") (name "unconnected-(编码器3-Pad5)") (class "Default")
      (node (ref "编码器3") (pin "5") (pinfunction "5_5") (pintype "unspecified+no_connect"))
    )
    (net (code "119") (name "unconnected-(编码器3-Pad6)") (class "Default")
      (node (ref "编码器3") (pin "6") (pinfunction "6_6") (pintype "unspecified+no_connect"))
    )
    (net (code "120") (name "unconnected-(编码器4-Pad5)") (class "Default")
      (node (ref "编码器4") (pin "5") (pinfunction "5_5") (pintype "unspecified+no_connect"))
    )
    (net (code "121") (name "unconnected-(编码器4-Pad6)") (class "Default")
      (node (ref "编码器4") (pin "6") (pinfunction "6_6") (pintype "unspecified+no_connect"))
    )
  )
)
